# SCHEMAT_P_YTY_G_WNEJ.net
KiCad netlist of a schematic drawn in EAGLE
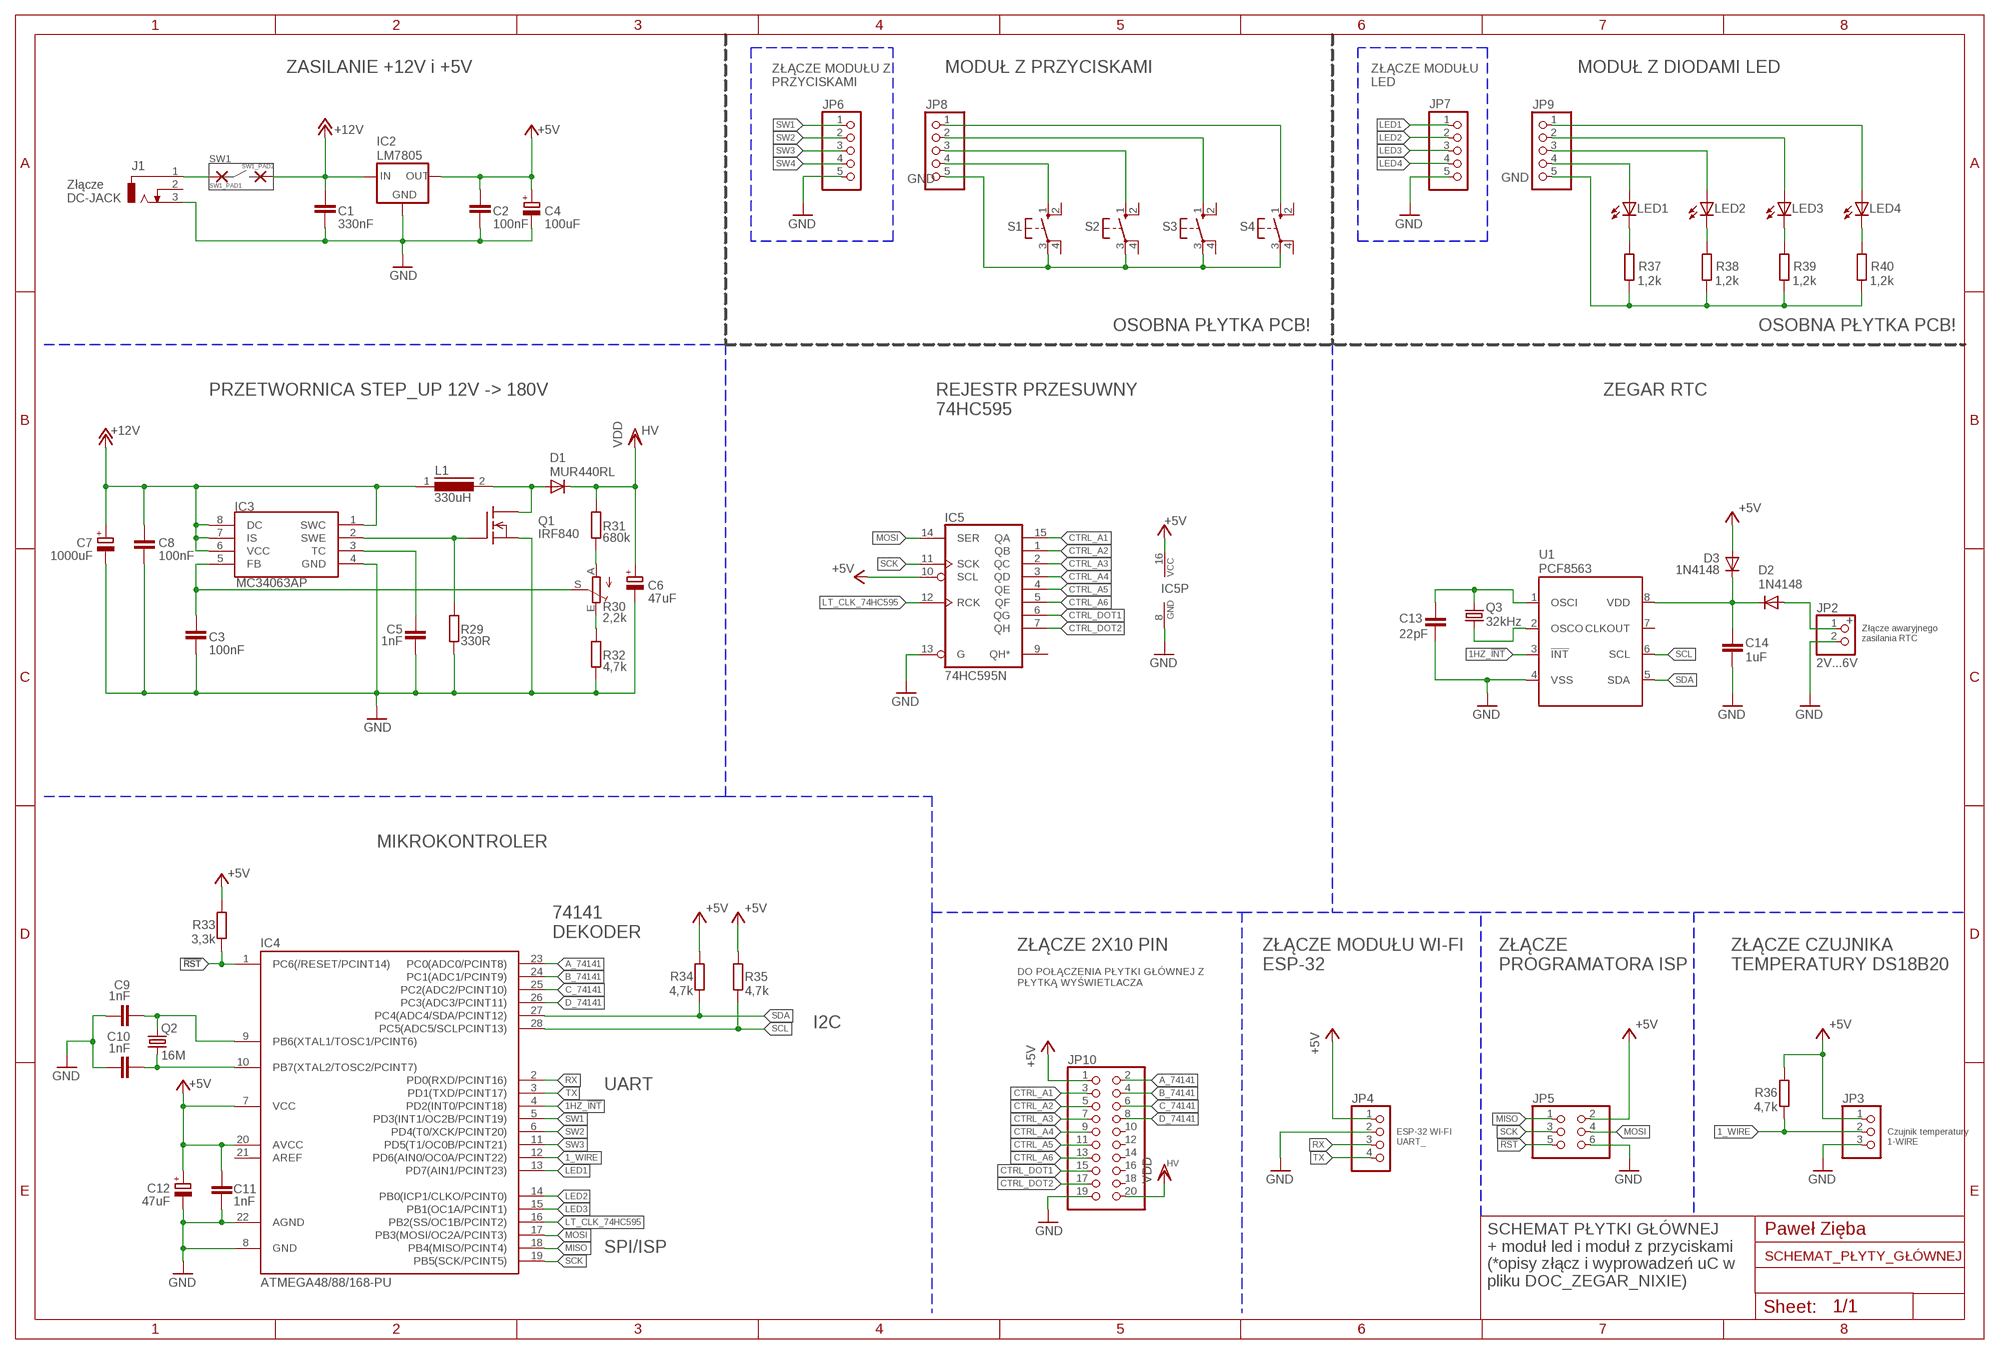
[diagram p0: schematic, sheet 1]

(export (version "E")
  (design (tool "Eeschema 10.0.6"))
  (components
    (comp (ref "C1")
      (value "330nF")
      (footprint "eagle-import:C050-045X075")
      (libsource (lib "eagle-import") (part "C-EU050-045X075"))
    )
    (comp (ref "C2")
      (value "100nF")
      (footprint "eagle-import:C050-045X075")
      (libsource (lib "eagle-import") (part "C-EU050-045X075"))
    )
    (comp (ref "C3")
      (value "100nF")
      (footprint "eagle-import:C050-045X075")
      (libsource (lib "eagle-import") (part "C-EU050-045X075"))
    )
    (comp (ref "C4")
      (value "100uF")
      (footprint "eagle-import:E5-13")
      (libsource (lib "eagle-import") (part "CPOL-EUE5-13"))
    )
    (comp (ref "C5")
      (value "1nF")
      (footprint "eagle-import:C050-045X075")
      (libsource (lib "eagle-import") (part "C-EU050-045X075"))
    )
    (comp (ref "C6")
      (value "47uF")
      (footprint "eagle-import:E5-13")
      (libsource (lib "eagle-import") (part "CPOL-EUE5-13"))
    )
    (comp (ref "C7")
      (value "1000uF")
      (footprint "eagle-import:E5-13")
      (libsource (lib "eagle-import") (part "CPOL-EUE5-13"))
    )
    (comp (ref "C8")
      (value "100nF")
      (footprint "eagle-import:C050-045X075")
      (libsource (lib "eagle-import") (part "C-EU050-045X075"))
    )
    (comp (ref "C9")
      (value "1nF")
      (footprint "eagle-import:C050-045X075")
      (libsource (lib "eagle-import") (part "C-EU050-045X075"))
    )
    (comp (ref "C10")
      (value "1nF")
      (footprint "eagle-import:C050-045X075")
      (libsource (lib "eagle-import") (part "C-EU050-045X075"))
    )
    (comp (ref "C11")
      (value "1nF")
      (footprint "eagle-import:C050-045X075")
      (libsource (lib "eagle-import") (part "C-EU050-045X075"))
    )
    (comp (ref "C12")
      (value "47uF")
      (footprint "eagle-import:E5-13")
      (libsource (lib "eagle-import") (part "CPOL-EUE5-13"))
    )
    (comp (ref "C13")
      (value "22pF")
      (footprint "eagle-import:C050-045X075")
      (libsource (lib "eagle-import") (part "C-EU050-045X075"))
    )
    (comp (ref "C14")
      (value "1uF")
      (footprint "eagle-import:C050-045X075")
      (libsource (lib "eagle-import") (part "C-EU050-045X075"))
    )
    (comp (ref "D1")
      (value "MUR440RL")
      (footprint "eagle-import:C2673")
      (libsource (lib "eagle-import") (part "MUR440RL"))
    )
    (comp (ref "D2")
      (value "1N4148")
      (footprint "eagle-import:DO35-10")
      (libsource (lib "eagle-import") (part "1N4148DO35-10"))
    )
    (comp (ref "D3")
      (value "1N4148")
      (footprint "eagle-import:DO35-10")
      (libsource (lib "eagle-import") (part "1N4148DO35-10"))
    )
    (comp (ref "IC2")
      (value "LM7805")
      (footprint "eagle-import:78XXS")
      (libsource (lib "eagle-import") (part "78XXS"))
    )
    (comp (ref "IC3")
      (value "MC34063AP")
      (footprint "eagle-import:DIL08")
      (fields (field (name "SPICEPREFIX") "X"))
      (libsource (lib "eagle-import") (part "MC34063AP"))
    )
    (comp (ref "IC4")
      (value "ATMEGA48/88/168-PU")
      (footprint "eagle-import:DIL28-3")
      (libsource (lib "eagle-import") (part "ATMEGA48/88/168-PU"))
    )
    (comp (ref "IC5")
      (value "74HC595N")
      (footprint "eagle-import:DIL16")
      (libsource (lib "eagle-import") (part "74595NHC"))
    )
    (comp (ref "J1")
      (value "DCJ0303")
      (footprint "eagle-import:DCJ0303")
      (libsource (lib "eagle-import") (part "DCJ0303"))
    )
    (comp (ref "JP2")
      (value "2V...6V")
      (footprint "eagle-import:1X02")
      (libsource (lib "eagle-import") (part "PINHD-1X2"))
    )
    (comp (ref "JP3")
      (value "PINHD-1X3")
      (footprint "eagle-import:1X03")
      (libsource (lib "eagle-import") (part "PINHD-1X3"))
    )
    (comp (ref "JP4")
      (value "PINHD-1X4")
      (footprint "eagle-import:1X04")
      (libsource (lib "eagle-import") (part "PINHD-1X4"))
    )
    (comp (ref "JP5")
      (value "PINHD-2X3")
      (footprint "eagle-import:2X03")
      (libsource (lib "eagle-import") (part "PINHD-2X3"))
    )
    (comp (ref "JP6")
      (value "PINHD-1X5")
      (footprint "eagle-import:1X05")
      (libsource (lib "eagle-import") (part "PINHD-1X5"))
    )
    (comp (ref "JP7")
      (value "PINHD-1X5")
      (footprint "eagle-import:1X05")
      (libsource (lib "eagle-import") (part "PINHD-1X5"))
    )
    (comp (ref "JP8")
      (value "PINHD-1X5")
      (footprint "eagle-import:1X05")
      (libsource (lib "eagle-import") (part "PINHD-1X5"))
    )
    (comp (ref "JP9")
      (value "PINHD-1X5")
      (footprint "eagle-import:1X05")
      (libsource (lib "eagle-import") (part "PINHD-1X5"))
    )
    (comp (ref "JP10")
      (value "PINHD-2X10")
      (footprint "eagle-import:2X10")
      (libsource (lib "eagle-import") (part "PINHD-2X10"))
    )
    (comp (ref "L1")
      (value "330uH")
      (footprint "eagle-import:SFT830S")
      (libsource (lib "eagle-import") (part "SFT830S"))
    )
    (comp (ref "LED1")
      (value "LED5MM")
      (footprint "eagle-import:LED5MM")
      (libsource (lib "eagle-import") (part "LED5MM"))
    )
    (comp (ref "LED2")
      (value "LED5MM")
      (footprint "eagle-import:LED5MM")
      (libsource (lib "eagle-import") (part "LED5MM"))
    )
    (comp (ref "LED3")
      (value "LED5MM")
      (footprint "eagle-import:LED5MM")
      (libsource (lib "eagle-import") (part "LED5MM"))
    )
    (comp (ref "LED4")
      (value "LED5MM")
      (footprint "eagle-import:LED5MM")
      (libsource (lib "eagle-import") (part "LED5MM"))
    )
    (comp (ref "Q1")
      (value "IRF840")
      (footprint "eagle-import:TO220")
      (libsource (lib "eagle-import") (part "IRF840"))
    )
    (comp (ref "Q2")
      (value "16M")
      (footprint "eagle-import:HC49U-V")
      (libsource (lib "eagle-import") (part "CRYSTALHC49U-V"))
    )
    (comp (ref "Q3")
      (value "32kHz")
      (footprint "eagle-import:TC26H")
      (libsource (lib "eagle-import") (part "CRYSTALTC26H"))
    )
    (comp (ref "R29")
      (value "330R")
      (footprint "eagle-import:204_7")
      (libsource (lib "eagle-import") (part "R-EU7"))
    )
    (comp (ref "R30")
      (value "2,2k")
      (footprint "eagle-import:CA6V")
      (libsource (lib "eagle-import") (part "TRIM_EU-CA6V"))
    )
    (comp (ref "R31")
      (value "680k")
      (footprint "eagle-import:204_7")
      (libsource (lib "eagle-import") (part "R-EU7"))
    )
    (comp (ref "R32")
      (value "4,7k")
      (footprint "eagle-import:204_7")
      (libsource (lib "eagle-import") (part "R-EU7"))
    )
    (comp (ref "R33")
      (value "3,3k")
      (footprint "eagle-import:204_7")
      (libsource (lib "eagle-import") (part "R-EU7"))
    )
    (comp (ref "R34")
      (value "4,7k")
      (footprint "eagle-import:204_7")
      (libsource (lib "eagle-import") (part "R-EU7"))
    )
    (comp (ref "R35")
      (value "4,7k")
      (footprint "eagle-import:204_7")
      (libsource (lib "eagle-import") (part "R-EU7"))
    )
    (comp (ref "R36")
      (value "4,7k")
      (footprint "eagle-import:204_7")
      (libsource (lib "eagle-import") (part "R-EU7"))
    )
    (comp (ref "R37")
      (value "1,2k")
      (footprint "eagle-import:204_7")
      (libsource (lib "eagle-import") (part "R-EU7"))
    )
    (comp (ref "R38")
      (value "1,2k")
      (footprint "eagle-import:204_7")
      (libsource (lib "eagle-import") (part "R-EU7"))
    )
    (comp (ref "R39")
      (value "1,2k")
      (footprint "eagle-import:204_7")
      (libsource (lib "eagle-import") (part "R-EU7"))
    )
    (comp (ref "R40")
      (value "1,2k")
      (footprint "eagle-import:204_7")
      (libsource (lib "eagle-import") (part "R-EU7"))
    )
    (comp (ref "S1")
      (value "10-XX")
      (footprint "eagle-import:B3F-10XX")
      (fields (field (name "MPN") "B3F-1000"))
      (libsource (lib "eagle-import") (part "10-XX"))
    )
    (comp (ref "S2")
      (value "10-XX")
      (footprint "eagle-import:B3F-10XX")
      (fields (field (name "MPN") "B3F-1000"))
      (libsource (lib "eagle-import") (part "10-XX"))
    )
    (comp (ref "S3")
      (value "10-XX")
      (footprint "eagle-import:B3F-10XX")
      (fields (field (name "MPN") "B3F-1000"))
      (libsource (lib "eagle-import") (part "10-XX"))
    )
    (comp (ref "S4")
      (value "10-XX")
      (footprint "eagle-import:B3F-10XX")
      (fields (field (name "MPN") "B3F-1000"))
      (libsource (lib "eagle-import") (part "10-XX"))
    )
    (comp (ref "SW1_PAD1")
      (value "3,81/1,4")
      (footprint "eagle-import:3,81_1,4")
      (libsource (lib "eagle-import") (part "3,81/1,4"))
    )
    (comp (ref "SW1_PAD2")
      (value "3,81/1,4")
      (footprint "eagle-import:3,81_1,4")
      (libsource (lib "eagle-import") (part "3,81/1,4"))
    )
    (comp (ref "U1")
      (value "PCF8563")
      (footprint "eagle-import:DIL08")
      (libsource (lib "eagle-import") (part "PCF8563"))
    )
  )
  (nets
    (net (code "1") (name "+5V") (class "Default")
      (node (ref "C11") (pin "2") (pinfunction "2_2") (pintype "passive"))
      (node (ref "C12") (pin "+") (pinfunction "+_+") (pintype "passive"))
      (node (ref "C2") (pin "1") (pinfunction "1_1") (pintype "passive"))
      (node (ref "C4") (pin "+") (pinfunction "+_+") (pintype "passive"))
      (node (ref "D3") (pin "A") (pinfunction "A_A") (pintype "passive"))
      (node (ref "IC2") (pin "OUT") (pinfunction "OUT_OUT") (pintype "passive"))
      (node (ref "IC4") (pin "20") (pinfunction "AVCC_20") (pintype "passive"))
      (node (ref "IC4") (pin "7") (pinfunction "VCC_7") (pintype "power_in"))
      (node (ref "IC5") (pin "10") (pinfunction "SCL_10") (pintype "input"))
      (node (ref "IC5") (pin "16") (pinfunction "VCC_16") (pintype "power_in"))
      (node (ref "JP10") (pin "1") (pinfunction "1_1") (pintype "passive"))
      (node (ref "JP3") (pin "1") (pinfunction "1_1") (pintype "passive"))
      (node (ref "JP4") (pin "1") (pinfunction "1_1") (pintype "passive"))
      (node (ref "JP5") (pin "2") (pinfunction "2_2") (pintype "passive"))
      (node (ref "R33") (pin "P$2") (pinfunction "2_P$2") (pintype "passive"))
      (node (ref "R34") (pin "P$2") (pinfunction "2_P$2") (pintype "passive"))
      (node (ref "R35") (pin "P$2") (pinfunction "2_P$2") (pintype "passive"))
      (node (ref "R36") (pin "P$2") (pinfunction "2_P$2") (pintype "passive"))
    )
    (net (code "2") (name "+12V") (class "Default")
      (node (ref "C1") (pin "1") (pinfunction "1_1") (pintype "passive"))
      (node (ref "C7") (pin "+") (pinfunction "+_+") (pintype "passive"))
      (node (ref "C8") (pin "1") (pinfunction "1_1") (pintype "passive"))
      (node (ref "IC2") (pin "IN") (pinfunction "IN_IN") (pintype "input"))
      (node (ref "IC3") (pin "1") (pinfunction "SWC_1") (pintype "passive"))
      (node (ref "IC3") (pin "6") (pinfunction "VCC_6") (pintype "passive"))
      (node (ref "IC3") (pin "7") (pinfunction "IS_7") (pintype "passive"))
      (node (ref "IC3") (pin "8") (pinfunction "DC_8") (pintype "passive"))
      (node (ref "L1") (pin "1") (pinfunction "1_1") (pintype "passive"))
      (node (ref "SW1_PAD2") (pin "1") (pinfunction "P_1") (pintype "passive"))
    )
    (net (code "3") (name "/1HZ_~{INT}") (class "Default")
      (node (ref "IC4") (pin "4") (pinfunction "PD2(INT0/PCINT18)_4") (pintype "bidirectional"))
      (node (ref "U1") (pin "3") (pinfunction "~{INT}_3") (pintype "bidirectional"))
    )
    (net (code "4") (name "/~{RST}") (class "Default")
      (node (ref "IC4") (pin "1") (pinfunction "PC6(/RESET/PCINT14)_1") (pintype "bidirectional"))
      (node (ref "JP5") (pin "5") (pinfunction "5_5") (pintype "passive"))
      (node (ref "R33") (pin "P$1") (pinfunction "1_P$1") (pintype "passive"))
    )
    (net (code "5") (name "1_WIRE") (class "Default")
      (node (ref "IC4") (pin "12") (pinfunction "PD6(AIN0/OC0A/PCINT22)_12") (pintype "bidirectional"))
      (node (ref "JP3") (pin "2") (pinfunction "2_2") (pintype "passive"))
      (node (ref "R36") (pin "P$1") (pinfunction "1_P$1") (pintype "passive"))
    )
    (net (code "6") (name "A_74141") (class "Default")
      (node (ref "IC4") (pin "23") (pinfunction "PC0(ADC0/PCINT8)_23") (pintype "bidirectional"))
      (node (ref "JP10") (pin "2") (pinfunction "2_2") (pintype "passive"))
    )
    (net (code "7") (name "B_74141") (class "Default")
      (node (ref "IC4") (pin "24") (pinfunction "PC1(ADC1/PCINT9)_24") (pintype "bidirectional"))
      (node (ref "JP10") (pin "4") (pinfunction "4_4") (pintype "passive"))
    )
    (net (code "8") (name "CTRL_A1") (class "Default")
      (node (ref "IC5") (pin "15") (pinfunction "QA_15") (pintype "tri_state"))
      (node (ref "JP10") (pin "3") (pinfunction "3_3") (pintype "passive"))
    )
    (net (code "9") (name "CTRL_A2") (class "Default")
      (node (ref "IC5") (pin "1") (pinfunction "QB_1") (pintype "tri_state"))
      (node (ref "JP10") (pin "5") (pinfunction "5_5") (pintype "passive"))
    )
    (net (code "10") (name "CTRL_A3") (class "Default")
      (node (ref "IC5") (pin "2") (pinfunction "QC_2") (pintype "tri_state"))
      (node (ref "JP10") (pin "7") (pinfunction "7_7") (pintype "passive"))
    )
    (net (code "11") (name "CTRL_A4") (class "Default")
      (node (ref "IC5") (pin "3") (pinfunction "QD_3") (pintype "tri_state"))
      (node (ref "JP10") (pin "9") (pinfunction "9_9") (pintype "passive"))
    )
    (net (code "12") (name "CTRL_A5") (class "Default")
      (node (ref "IC5") (pin "4") (pinfunction "QE_4") (pintype "tri_state"))
      (node (ref "JP10") (pin "11") (pinfunction "11_11") (pintype "passive"))
    )
    (net (code "13") (name "CTRL_A6") (class "Default")
      (node (ref "IC5") (pin "5") (pinfunction "QF_5") (pintype "tri_state"))
      (node (ref "JP10") (pin "13") (pinfunction "13_13") (pintype "passive"))
    )
    (net (code "14") (name "CTRL_DOT1") (class "Default")
      (node (ref "IC5") (pin "6") (pinfunction "QG_6") (pintype "tri_state"))
      (node (ref "JP10") (pin "15") (pinfunction "15_15") (pintype "passive"))
    )
    (net (code "15") (name "CTRL_DOT2") (class "Default")
      (node (ref "IC5") (pin "7") (pinfunction "QH_7") (pintype "tri_state"))
      (node (ref "JP10") (pin "17") (pinfunction "17_17") (pintype "passive"))
    )
    (net (code "16") (name "C_74141") (class "Default")
      (node (ref "IC4") (pin "25") (pinfunction "PC2(ADC2/PCINT10)_25") (pintype "bidirectional"))
      (node (ref "JP10") (pin "6") (pinfunction "6_6") (pintype "passive"))
    )
    (net (code "17") (name "D_74141") (class "Default")
      (node (ref "IC4") (pin "26") (pinfunction "PC3(ADC3/PCINT11)_26") (pintype "bidirectional"))
      (node (ref "JP10") (pin "8") (pinfunction "8_8") (pintype "passive"))
    )
    (net (code "18") (name "GND") (class "Default")
      (node (ref "C1") (pin "2") (pinfunction "2_2") (pintype "passive"))
      (node (ref "C10") (pin "1") (pinfunction "1_1") (pintype "passive"))
      (node (ref "C11") (pin "1") (pinfunction "1_1") (pintype "passive"))
      (node (ref "C12") (pin "-") (pinfunction "-_-") (pintype "passive"))
      (node (ref "C13") (pin "2") (pinfunction "2_2") (pintype "passive"))
      (node (ref "C14") (pin "2") (pinfunction "2_2") (pintype "passive"))
      (node (ref "C2") (pin "2") (pinfunction "2_2") (pintype "passive"))
      (node (ref "C3") (pin "2") (pinfunction "2_2") (pintype "passive"))
      (node (ref "C4") (pin "-") (pinfunction "-_-") (pintype "passive"))
      (node (ref "C5") (pin "2") (pinfunction "2_2") (pintype "passive"))
      (node (ref "C6") (pin "-") (pinfunction "-_-") (pintype "passive"))
      (node (ref "C7") (pin "-") (pinfunction "-_-") (pintype "passive"))
      (node (ref "C8") (pin "2") (pinfunction "2_2") (pintype "passive"))
      (node (ref "C9") (pin "1") (pinfunction "1_1") (pintype "passive"))
      (node (ref "IC2") (pin "GND") (pinfunction "GND_GND") (pintype "input"))
      (node (ref "IC3") (pin "4") (pinfunction "GND_4") (pintype "passive"))
      (node (ref "IC4") (pin "22") (pinfunction "AGND_22") (pintype "power_in"))
      (node (ref "IC4") (pin "8") (pinfunction "GND_8") (pintype "power_in"))
      (node (ref "IC5") (pin "13") (pinfunction "G_13") (pintype "input"))
      (node (ref "IC5") (pin "8") (pinfunction "GND_8") (pintype "power_in"))
      (node (ref "J1") (pin "3") (pinfunction "3_3") (pintype "passive"))
      (node (ref "JP10") (pin "19") (pinfunction "19_19") (pintype "passive"))
      (node (ref "JP2") (pin "2") (pinfunction "2_2") (pintype "passive"))
      (node (ref "JP3") (pin "3") (pinfunction "3_3") (pintype "passive"))
      (node (ref "JP4") (pin "2") (pinfunction "2_2") (pintype "passive"))
      (node (ref "JP5") (pin "6") (pinfunction "6_6") (pintype "passive"))
      (node (ref "JP6") (pin "5") (pinfunction "5_5") (pintype "passive"))
      (node (ref "JP7") (pin "5") (pinfunction "5_5") (pintype "passive"))
      (node (ref "Q1") (pin "3") (pinfunction "S_3") (pintype "passive"))
      (node (ref "R29") (pin "P$1") (pinfunction "1_P$1") (pintype "passive"))
      (node (ref "R32") (pin "P$1") (pinfunction "1_P$1") (pintype "passive"))
      (node (ref "U1") (pin "4") (pinfunction "VSS_4") (pintype "bidirectional"))
    )
    (net (code "19") (name "LED1") (class "Default")
      (node (ref "IC4") (pin "13") (pinfunction "PD7(AIN1/PCINT23)_13") (pintype "bidirectional"))
      (node (ref "JP7") (pin "1") (pinfunction "1_1") (pintype "passive"))
    )
    (net (code "20") (name "LED2") (class "Default")
      (node (ref "IC4") (pin "14") (pinfunction "PB0(ICP1/CLKO/PCINT0)_14") (pintype "bidirectional"))
      (node (ref "JP7") (pin "2") (pinfunction "2_2") (pintype "passive"))
    )
    (net (code "21") (name "LED3") (class "Default")
      (node (ref "IC4") (pin "15") (pinfunction "PB1(OC1A/PCINT1)_15") (pintype "bidirectional"))
      (node (ref "JP7") (pin "3") (pinfunction "3_3") (pintype "passive"))
    )
    (net (code "22") (name "LED4") (class "Default")
      (node (ref "JP7") (pin "4") (pinfunction "4_4") (pintype "passive"))
    )
    (net (code "23") (name "LT_CLK_74HC595") (class "Default")
      (node (ref "IC4") (pin "16") (pinfunction "PB2(SS/OC1B/PCINT2)_16") (pintype "bidirectional"))
      (node (ref "IC5") (pin "12") (pinfunction "RCK_12") (pintype "input"))
    )
    (net (code "24") (name "MISO") (class "Default")
      (node (ref "IC4") (pin "18") (pinfunction "PB4(MISO/PCINT4)_18") (pintype "bidirectional"))
      (node (ref "JP5") (pin "1") (pinfunction "1_1") (pintype "passive"))
    )
    (net (code "25") (name "MOSI") (class "Default")
      (node (ref "IC4") (pin "17") (pinfunction "PB3(MOSI/OC2A/PCINT3)_17") (pintype "bidirectional"))
      (node (ref "IC5") (pin "14") (pinfunction "SER_14") (pintype "input"))
      (node (ref "JP5") (pin "4") (pinfunction "4_4") (pintype "passive"))
    )
    (net (code "26") (name "Net-(D2-PadA)") (class "Default")
      (node (ref "D2") (pin "A") (pinfunction "A_A") (pintype "passive"))
      (node (ref "JP2") (pin "1") (pinfunction "1_1") (pintype "passive"))
    )
    (net (code "27") (name "Net-(IC3-FB)") (class "Default")
      (node (ref "C3") (pin "1") (pinfunction "1_1") (pintype "passive"))
      (node (ref "IC3") (pin "5") (pinfunction "FB_5") (pintype "passive"))
      (node (ref "R30") (pin "S") (pinfunction "S_S") (pintype "passive"))
    )
    (net (code "28") (name "Net-(IC3-SWE)") (class "Default")
      (node (ref "IC3") (pin "2") (pinfunction "SWE_2") (pintype "passive"))
      (node (ref "Q1") (pin "1") (pinfunction "G_1") (pintype "passive"))
      (node (ref "R29") (pin "P$2") (pinfunction "2_P$2") (pintype "passive"))
    )
    (net (code "29") (name "Net-(IC3-TC)") (class "Default")
      (node (ref "C5") (pin "1") (pinfunction "1_1") (pintype "passive"))
      (node (ref "IC3") (pin "3") (pinfunction "TC_3") (pintype "passive"))
    )
    (net (code "30") (name "Net-(IC4-PB6(XTAL1{slash}TOSC1{slash}PCINT6))") (class "Default")
      (node (ref "C9") (pin "2") (pinfunction "2_2") (pintype "passive"))
      (node (ref "IC4") (pin "9") (pinfunction "PB6(XTAL1/TOSC1/PCINT6)_9") (pintype "bidirectional"))
      (node (ref "Q2") (pin "1") (pinfunction "1_1") (pintype "passive"))
    )
    (net (code "31") (name "Net-(IC4-PB7(XTAL2{slash}TOSC2{slash}PCINT7))") (class "Default")
      (node (ref "C10") (pin "2") (pinfunction "2_2") (pintype "passive"))
      (node (ref "IC4") (pin "10") (pinfunction "PB7(XTAL2/TOSC2/PCINT7)_10") (pintype "bidirectional"))
      (node (ref "Q2") (pin "2") (pinfunction "2_2") (pintype "passive"))
    )
    (net (code "32") (name "Net-(JP9-Pad1)") (class "Default")
      (node (ref "JP9") (pin "1") (pinfunction "1_1") (pintype "passive"))
      (node (ref "LED4") (pin "A") (pinfunction "A_A") (pintype "passive"))
    )
    (net (code "33") (name "Net-(JP9-Pad2)") (class "Default")
      (node (ref "JP9") (pin "2") (pinfunction "2_2") (pintype "passive"))
      (node (ref "LED3") (pin "A") (pinfunction "A_A") (pintype "passive"))
    )
    (net (code "34") (name "Net-(JP9-Pad3)") (class "Default")
      (node (ref "JP9") (pin "3") (pinfunction "3_3") (pintype "passive"))
      (node (ref "LED2") (pin "A") (pinfunction "A_A") (pintype "passive"))
    )
    (net (code "35") (name "Net-(JP9-Pad4)") (class "Default")
      (node (ref "JP9") (pin "4") (pinfunction "4_4") (pintype "passive"))
      (node (ref "LED1") (pin "A") (pinfunction "A_A") (pintype "passive"))
    )
    (net (code "36") (name "Net-(LED1-C)") (class "Default")
      (node (ref "LED1") (pin "K") (pinfunction "C_K") (pintype "passive"))
      (node (ref "R37") (pin "P$2") (pinfunction "2_P$2") (pintype "passive"))
    )
    (net (code "37") (name "Net-(LED2-C)") (class "Default")
      (node (ref "LED2") (pin "K") (pinfunction "C_K") (pintype "passive"))
      (node (ref "R38") (pin "P$2") (pinfunction "2_P$2") (pintype "passive"))
    )
    (net (code "38") (name "Net-(LED3-C)") (class "Default")
      (node (ref "LED3") (pin "K") (pinfunction "C_K") (pintype "passive"))
      (node (ref "R39") (pin "P$2") (pinfunction "2_P$2") (pintype "passive"))
    )
    (net (code "39") (name "Net-(LED4-C)") (class "Default")
      (node (ref "LED4") (pin "K") (pinfunction "C_K") (pintype "passive"))
      (node (ref "R40") (pin "P$2") (pinfunction "2_P$2") (pintype "passive"))
    )
    (net (code "40") (name "Net-(Q1-D)") (class "Default")
      (node (ref "D1") (pin "A") (pinfunction "A_A") (pintype "passive"))
      (node (ref "L1") (pin "2") (pinfunction "2_2") (pintype "passive"))
      (node (ref "Q1") (pin "2") (pinfunction "D_2") (pintype "passive"))
    )
    (net (code "41") (name "Net-(R31-1)") (class "Default")
      (node (ref "R30") (pin "A") (pinfunction "A_A") (pintype "passive"))
      (node (ref "R31") (pin "P$1") (pinfunction "1_P$1") (pintype "passive"))
    )
    (net (code "42") (name "Net-(R32-2)") (class "Default")
      (node (ref "R30") (pin "E") (pinfunction "E_E") (pintype "passive"))
      (node (ref "R32") (pin "P$2") (pinfunction "2_P$2") (pintype "passive"))
    )
    (net (code "43") (name "Net-(R37-1)") (class "Default")
      (node (ref "JP9") (pin "5") (pinfunction "5_5") (pintype "passive"))
      (node (ref "R37") (pin "P$1") (pinfunction "1_P$1") (pintype "passive"))
      (node (ref "R38") (pin "P$1") (pinfunction "1_P$1") (pintype "passive"))
      (node (ref "R39") (pin "P$1") (pinfunction "1_P$1") (pintype "passive"))
      (node (ref "R40") (pin "P$1") (pinfunction "1_P$1") (pintype "passive"))
    )
    (net (code "44") (name "Net-(S1-P)") (class "Default")
      (node (ref "JP8") (pin "5") (pinfunction "5_5") (pintype "passive"))
      (node (ref "S1") (pin "3") (pinfunction "P_3") (pintype "passive"))
      (node (ref "S2") (pin "3") (pinfunction "P_3") (pintype "passive"))
      (node (ref "S3") (pin "3") (pinfunction "P_3") (pintype "passive"))
      (node (ref "S4") (pin "3") (pinfunction "P_3") (pintype "passive"))
    )
    (net (code "45") (name "Net-(S1-S)") (class "Default")
      (node (ref "JP8") (pin "4") (pinfunction "4_4") (pintype "passive"))
      (node (ref "S1") (pin "1") (pinfunction "S_1") (pintype "passive"))
    )
    (net (code "46") (name "Net-(S2-S)") (class "Default")
      (node (ref "JP8") (pin "3") (pinfunction "3_3") (pintype "passive"))
      (node (ref "S2") (pin "1") (pinfunction "S_1") (pintype "passive"))
    )
    (net (code "47") (name "Net-(S3-S)") (class "Default")
      (node (ref "JP8") (pin "2") (pinfunction "2_2") (pintype "passive"))
      (node (ref "S3") (pin "1") (pinfunction "S_1") (pintype "passive"))
    )
    (net (code "48") (name "Net-(S4-S)") (class "Default")
      (node (ref "JP8") (pin "1") (pinfunction "1_1") (pintype "passive"))
      (node (ref "S4") (pin "1") (pinfunction "S_1") (pintype "passive"))
    )
    (net (code "49") (name "Net-(SW1_PAD1-P)") (class "Default")
      (node (ref "J1") (pin "1") (pinfunction "1_1") (pintype "passive"))
      (node (ref "SW1_PAD1") (pin "1") (pinfunction "P_1") (pintype "passive"))
    )
    (net (code "50") (name "Net-(U1-OSCI)") (class "Default")
      (node (ref "C13") (pin "1") (pinfunction "1_1") (pintype "passive"))
      (node (ref "Q3") (pin "2") (pinfunction "2_2") (pintype "passive"))
      (node (ref "U1") (pin "1") (pinfunction "OSCI_1") (pintype "bidirectional"))
    )
    (net (code "51") (name "Net-(U1-OSCO)") (class "Default")
      (node (ref "Q3") (pin "1") (pinfunction "1_1") (pintype "passive"))
      (node (ref "U1") (pin "2") (pinfunction "OSCO_2") (pintype "bidirectional"))
    )
    (net (code "52") (name "Net-(U1-VDD)") (class "Default")
      (node (ref "C14") (pin "1") (pinfunction "1_1") (pintype "passive"))
      (node (ref "D2") (pin "C") (pinfunction "C_C") (pintype "passive"))
      (node (ref "D3") (pin "C") (pinfunction "C_C") (pintype "passive"))
      (node (ref "U1") (pin "8") (pinfunction "VDD_8") (pintype "bidirectional"))
    )
    (net (code "53") (name "RX") (class "Default")
      (node (ref "IC4") (pin "2") (pinfunction "PD0(RXD/PCINT16)_2") (pintype "bidirectional"))
      (node (ref "JP4") (pin "3") (pinfunction "3_3") (pintype "passive"))
    )
    (net (code "54") (name "SCK") (class "Default")
      (node (ref "IC4") (pin "19") (pinfunction "PB5(SCK/PCINT5)_19") (pintype "bidirectional"))
      (node (ref "IC5") (pin "11") (pinfunction "SCK_11") (pintype "input"))
      (node (ref "JP5") (pin "3") (pinfunction "3_3") (pintype "passive"))
    )
    (net (code "55") (name "SCL") (class "Default")
      (node (ref "IC4") (pin "28") (pinfunction "PC5(ADC5/SCLPCINT13)_28") (pintype "bidirectional"))
      (node (ref "R35") (pin "P$1") (pinfunction "1_P$1") (pintype "passive"))
      (node (ref "U1") (pin "6") (pinfunction "SCL_6") (pintype "bidirectional"))
    )
    (net (code "56") (name "SDA") (class "Default")
      (node (ref "IC4") (pin "27") (pinfunction "PC4(ADC4/SDA/PCINT12)_27") (pintype "bidirectional"))
      (node (ref "R34") (pin "P$1") (pinfunction "1_P$1") (pintype "passive"))
      (node (ref "U1") (pin "5") (pinfunction "SDA_5") (pintype "bidirectional"))
    )
    (net (code "57") (name "SW1") (class "Default")
      (node (ref "IC4") (pin "5") (pinfunction "PD3(INT1/OC2B/PCINT19)_5") (pintype "bidirectional"))
      (node (ref "JP6") (pin "1") (pinfunction "1_1") (pintype "passive"))
    )
    (net (code "58") (name "SW2") (class "Default")
      (node (ref "IC4") (pin "6") (pinfunction "PD4(T0/XCK/PCINT20)_6") (pintype "bidirectional"))
      (node (ref "JP6") (pin "2") (pinfunction "2_2") (pintype "passive"))
    )
    (net (code "59") (name "SW3") (class "Default")
      (node (ref "IC4") (pin "11") (pinfunction "PD5(T1/OC0B/PCINT21)_11") (pintype "bidirectional"))
      (node (ref "JP6") (pin "3") (pinfunction "3_3") (pintype "passive"))
    )
    (net (code "60") (name "SW4") (class "Default")
      (node (ref "JP6") (pin "4") (pinfunction "4_4") (pintype "passive"))
    )
    (net (code "61") (name "TX") (class "Default")
      (node (ref "IC4") (pin "3") (pinfunction "PD1(TXD/PCINT17)_3") (pintype "bidirectional"))
      (node (ref "JP4") (pin "4") (pinfunction "4_4") (pintype "passive"))
    )
    (net (code "62") (name "VDD") (class "Default")
      (node (ref "C6") (pin "+") (pinfunction "+_+") (pintype "passive"))
      (node (ref "D1") (pin "C") (pinfunction "C_C") (pintype "passive"))
      (node (ref "JP10") (pin "20") (pinfunction "20_20") (pintype "passive"))
      (node (ref "R31") (pin "P$2") (pinfunction "2_P$2") (pintype "passive"))
    )
    (net (code "63") (name "unconnected-(IC4-AREF-Pad21)") (class "Default")
      (node (ref "IC4") (pin "21") (pinfunction "AREF_21") (pintype "passive"))
    )
    (net (code "64") (name "unconnected-(IC5A-QH*-Pad9)") (class "Default")
      (node (ref "IC5") (pin "9") (pinfunction "QH*_9") (pintype "tri_state"))
    )
    (net (code "65") (name "unconnected-(J1-Pad2)") (class "Default")
      (node (ref "J1") (pin "2") (pinfunction "2_2") (pintype "passive"))
    )
    (net (code "66") (name "unconnected-(JP10-Pad10)") (class "Default")
      (node (ref "JP10") (pin "10") (pinfunction "10_10") (pintype "passive"))
    )
    (net (code "67") (name "unconnected-(JP10-Pad12)") (class "Default")
      (node (ref "JP10") (pin "12") (pinfunction "12_12") (pintype "passive"))
    )
    (net (code "68") (name "unconnected-(JP10-Pad14)") (class "Default")
      (node (ref "JP10") (pin "14") (pinfunction "14_14") (pintype "passive"))
    )
    (net (code "69") (name "unconnected-(JP10-Pad16)") (class "Default")
      (node (ref "JP10") (pin "16") (pinfunction "16_16") (pintype "passive"))
    )
    (net (code "70") (name "unconnected-(JP10-Pad18)") (class "Default")
      (node (ref "JP10") (pin "18") (pinfunction "18_18") (pintype "passive"))
    )
    (net (code "71") (name "unconnected-(S1-P1-Pad4)") (class "Default")
      (node (ref "S1") (pin "4") (pinfunction "P1_4") (pintype "passive"))
    )
    (net (code "72") (name "unconnected-(S1-S1-Pad2)") (class "Default")
      (node (ref "S1") (pin "2") (pinfunction "S1_2") (pintype "passive"))
    )
    (net (code "73") (name "unconnected-(S2-P1-Pad4)") (class "Default")
      (node (ref "S2") (pin "4") (pinfunction "P1_4") (pintype "passive"))
    )
    (net (code "74") (name "unconnected-(S2-S1-Pad2)") (class "Default")
      (node (ref "S2") (pin "2") (pinfunction "S1_2") (pintype "passive"))
    )
    (net (code "75") (name "unconnected-(S3-P1-Pad4)") (class "Default")
      (node (ref "S3") (pin "4") (pinfunction "P1_4") (pintype "passive"))
    )
    (net (code "76") (name "unconnected-(S3-S1-Pad2)") (class "Default")
      (node (ref "S3") (pin "2") (pinfunction "S1_2") (pintype "passive"))
    )
    (net (code "77") (name "unconnected-(S4-P1-Pad4)") (class "Default")
      (node (ref "S4") (pin "4") (pinfunction "P1_4") (pintype "passive"))
    )
    (net (code "78") (name "unconnected-(S4-S1-Pad2)") (class "Default")
      (node (ref "S4") (pin "2") (pinfunction "S1_2") (pintype "passive"))
    )
    (net (code "79") (name "unconnected-(U1-CLKOUT-Pad7)") (class "Default")
      (node (ref "U1") (pin "7") (pinfunction "CLKOUT_7") (pintype "bidirectional"))
    )
  )
)
